# 5volt_rail.net
KiCad netlist of a schematic drawn in EAGLE
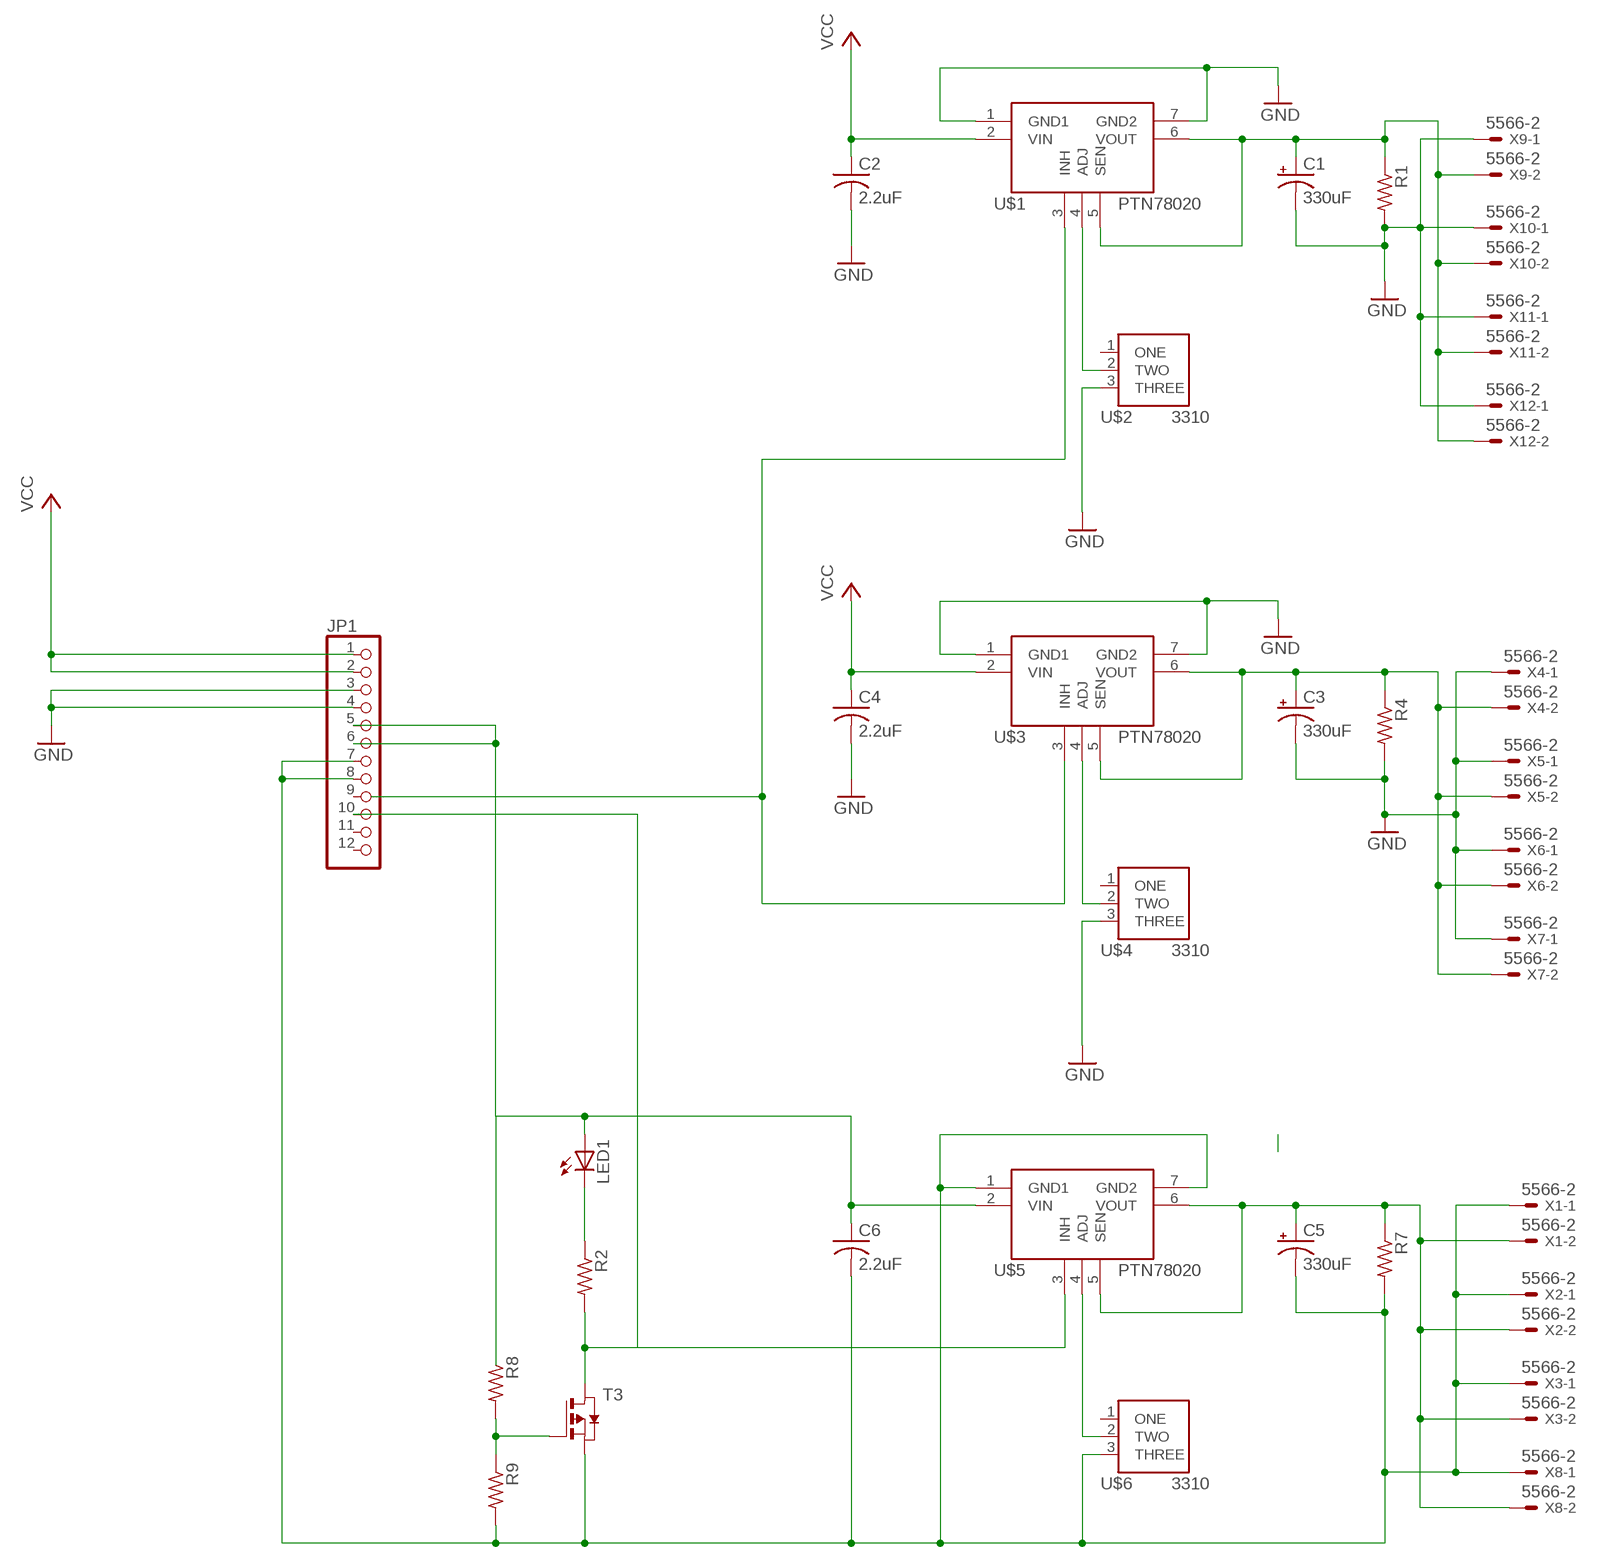
[diagram p0: schematic, sheet 1]

(export (version "E")
  (design (tool "Eeschema 10.0.6"))
  (components
    (comp (ref "C1")
      (value "330uF")
      (footprint "eagle-import:E5-10,5")
      (libsource (lib "eagle-import") (part "CPOL-USE5-10.5"))
    )
    (comp (ref "C2")
      (value "2.2uF")
      (footprint "eagle-import:C0805")
      (libsource (lib "eagle-import") (part "C-USC0805"))
    )
    (comp (ref "C3")
      (value "330uF")
      (footprint "eagle-import:E5-10,5")
      (libsource (lib "eagle-import") (part "CPOL-USE5-10.5"))
    )
    (comp (ref "C4")
      (value "2.2uF")
      (footprint "eagle-import:C0805")
      (libsource (lib "eagle-import") (part "C-USC0805"))
    )
    (comp (ref "C5")
      (value "330uF")
      (footprint "eagle-import:E5-10,5")
      (libsource (lib "eagle-import") (part "CPOL-USE5-10.5"))
    )
    (comp (ref "C6")
      (value "2.2uF")
      (footprint "eagle-import:C0805")
      (libsource (lib "eagle-import") (part "C-USC0805"))
    )
    (comp (ref "JP1")
      (value "PINHD-1X12")
      (footprint "eagle-import:1X12")
      (libsource (lib "eagle-import") (part "PINHD-1X12"))
    )
    (comp (ref "LED1")
      (value "LED5MM")
      (footprint "eagle-import:LED5MM")
      (libsource (lib "eagle-import") (part "LED5MM"))
    )
    (comp (ref "R1")
      (value "R-US_M0805")
      (footprint "eagle-import:M0805")
      (libsource (lib "eagle-import") (part "R-US_M0805"))
    )
    (comp (ref "R2")
      (value "R-US_M0805")
      (footprint "eagle-import:M0805")
      (libsource (lib "eagle-import") (part "R-US_M0805"))
    )
    (comp (ref "R4")
      (value "R-US_M0805")
      (footprint "eagle-import:M0805")
      (libsource (lib "eagle-import") (part "R-US_M0805"))
    )
    (comp (ref "R7")
      (value "R-US_M0805")
      (footprint "eagle-import:M0805")
      (libsource (lib "eagle-import") (part "R-US_M0805"))
    )
    (comp (ref "R8")
      (value "R-US_M0805")
      (footprint "eagle-import:M0805")
      (libsource (lib "eagle-import") (part "R-US_M0805"))
    )
    (comp (ref "R9")
      (value "R-US_M0805")
      (footprint "eagle-import:M0805")
      (libsource (lib "eagle-import") (part "R-US_M0805"))
    )
    (comp (ref "T3")
      (value "PMOSSOT223")
      (footprint "eagle-import:SOT223")
      (libsource (lib "eagle-import") (part "PMOSSOT223"))
    )
    (comp (ref "U$1")
      (value "PTH78020-SMD")
      (footprint "eagle-import:PTN78020-SND")
      (libsource (lib "eagle-import") (part "PTH78020-SMD"))
    )
    (comp (ref "U$2")
      (value "3310-001")
      (footprint "eagle-import:3310-001-TH")
      (libsource (lib "eagle-import") (part "3310-001"))
    )
    (comp (ref "U$3")
      (value "PTH78020-SMD")
      (footprint "eagle-import:PTN78020-SND")
      (libsource (lib "eagle-import") (part "PTH78020-SMD"))
    )
    (comp (ref "U$4")
      (value "3310-001")
      (footprint "eagle-import:3310-001-TH")
      (libsource (lib "eagle-import") (part "3310-001"))
    )
    (comp (ref "U$5")
      (value "PTH78020-SMD")
      (footprint "eagle-import:PTN78020-SND")
      (libsource (lib "eagle-import") (part "PTH78020-SMD"))
    )
    (comp (ref "U$6")
      (value "3310-001")
      (footprint "eagle-import:3310-001-TH")
      (libsource (lib "eagle-import") (part "3310-001"))
    )
    (comp (ref "X1")
      (value "5566-2")
      (footprint "eagle-import:5566-2")
      (libsource (lib "eagle-import") (part "5566-2"))
    )
    (comp (ref "X2")
      (value "5566-2")
      (footprint "eagle-import:5566-2")
      (libsource (lib "eagle-import") (part "5566-2"))
    )
    (comp (ref "X3")
      (value "5566-2")
      (footprint "eagle-import:5566-2")
      (libsource (lib "eagle-import") (part "5566-2"))
    )
    (comp (ref "X4")
      (value "5566-2")
      (footprint "eagle-import:5566-2")
      (libsource (lib "eagle-import") (part "5566-2"))
    )
    (comp (ref "X5")
      (value "5566-2")
      (footprint "eagle-import:5566-2")
      (libsource (lib "eagle-import") (part "5566-2"))
    )
    (comp (ref "X6")
      (value "5566-2")
      (footprint "eagle-import:5566-2")
      (libsource (lib "eagle-import") (part "5566-2"))
    )
    (comp (ref "X7")
      (value "5566-2")
      (footprint "eagle-import:5566-2")
      (libsource (lib "eagle-import") (part "5566-2"))
    )
    (comp (ref "X8")
      (value "5566-2")
      (footprint "eagle-import:5566-2")
      (libsource (lib "eagle-import") (part "5566-2"))
    )
    (comp (ref "X9")
      (value "5566-2")
      (footprint "eagle-import:5566-2")
      (libsource (lib "eagle-import") (part "5566-2"))
    )
    (comp (ref "X10")
      (value "5566-2")
      (footprint "eagle-import:5566-2")
      (libsource (lib "eagle-import") (part "5566-2"))
    )
    (comp (ref "X11")
      (value "5566-2")
      (footprint "eagle-import:5566-2")
      (libsource (lib "eagle-import") (part "5566-2"))
    )
    (comp (ref "X12")
      (value "5566-2")
      (footprint "eagle-import:5566-2")
      (libsource (lib "eagle-import") (part "5566-2"))
    )
  )
  (nets
    (net (code "1") (name "GND") (class "Default")
      (node (ref "C1") (pin "-") (pinfunction "-_-") (pintype "passive"))
      (node (ref "C2") (pin "2") (pinfunction "2_2") (pintype "passive"))
      (node (ref "C3") (pin "-") (pinfunction "-_-") (pintype "passive"))
      (node (ref "C4") (pin "2") (pinfunction "2_2") (pintype "passive"))
      (node (ref "JP1") (pin "3") (pinfunction "3_3") (pintype "passive"))
      (node (ref "JP1") (pin "4") (pinfunction "4_4") (pintype "passive"))
      (node (ref "R1") (pin "2") (pinfunction "2_2") (pintype "passive"))
      (node (ref "R4") (pin "2") (pinfunction "2_2") (pintype "passive"))
      (node (ref "U$1") (pin "1") (pinfunction "GND1_1") (pintype "bidirectional"))
      (node (ref "U$1") (pin "7") (pinfunction "GND2_7") (pintype "bidirectional"))
      (node (ref "U$2") (pin "3") (pinfunction "THREE_3") (pintype "bidirectional"))
      (node (ref "U$3") (pin "1") (pinfunction "GND1_1") (pintype "bidirectional"))
      (node (ref "U$3") (pin "7") (pinfunction "GND2_7") (pintype "bidirectional"))
      (node (ref "U$4") (pin "3") (pinfunction "THREE_3") (pintype "bidirectional"))
      (node (ref "X10") (pin "1") (pinfunction "S_1") (pintype "passive"))
      (node (ref "X11") (pin "1") (pinfunction "S_1") (pintype "passive"))
      (node (ref "X12") (pin "1") (pinfunction "S_1") (pintype "passive"))
      (node (ref "X4") (pin "1") (pinfunction "S_1") (pintype "passive"))
      (node (ref "X5") (pin "1") (pinfunction "S_1") (pintype "passive"))
      (node (ref "X6") (pin "1") (pinfunction "S_1") (pintype "passive"))
      (node (ref "X7") (pin "1") (pinfunction "S_1") (pintype "passive"))
      (node (ref "X9") (pin "1") (pinfunction "S_1") (pintype "passive"))
    )
    (net (code "2") (name "Net-(LED1-C)") (class "Default")
      (node (ref "LED1") (pin "K") (pinfunction "C_K") (pintype "passive"))
      (node (ref "R2") (pin "1") (pinfunction "1_1") (pintype "passive"))
    )
    (net (code "3") (name "Net-(T3-G)") (class "Default")
      (node (ref "R8") (pin "2") (pinfunction "2_2") (pintype "passive"))
      (node (ref "R9") (pin "1") (pinfunction "1_1") (pintype "passive"))
      (node (ref "T3") (pin "1") (pinfunction "G_1") (pintype "passive"))
    )
    (net (code "4") (name "Net-(T3-S)") (class "Default")
      (node (ref "C5") (pin "-") (pinfunction "-_-") (pintype "passive"))
      (node (ref "C6") (pin "2") (pinfunction "2_2") (pintype "passive"))
      (node (ref "JP1") (pin "7") (pinfunction "7_7") (pintype "passive"))
      (node (ref "JP1") (pin "8") (pinfunction "8_8") (pintype "passive"))
      (node (ref "R7") (pin "2") (pinfunction "2_2") (pintype "passive"))
      (node (ref "R9") (pin "2") (pinfunction "2_2") (pintype "passive"))
      (node (ref "T3") (pin "3") (pinfunction "S_3") (pintype "passive"))
      (node (ref "U$5") (pin "1") (pinfunction "GND1_1") (pintype "bidirectional"))
      (node (ref "U$5") (pin "7") (pinfunction "GND2_7") (pintype "bidirectional"))
      (node (ref "U$6") (pin "3") (pinfunction "THREE_3") (pintype "bidirectional"))
      (node (ref "X1") (pin "1") (pinfunction "S_1") (pintype "passive"))
      (node (ref "X2") (pin "1") (pinfunction "S_1") (pintype "passive"))
      (node (ref "X3") (pin "1") (pinfunction "S_1") (pintype "passive"))
      (node (ref "X8") (pin "1") (pinfunction "S_1") (pintype "passive"))
    )
    (net (code "5") (name "Net-(U$1-ADJ)") (class "Default")
      (node (ref "U$1") (pin "4") (pinfunction "ADJ_4") (pintype "bidirectional"))
      (node (ref "U$2") (pin "2") (pinfunction "TWO_2") (pintype "bidirectional"))
    )
    (net (code "6") (name "Net-(U$1-INH)") (class "Default")
      (node (ref "U$1") (pin "3") (pinfunction "INH_3") (pintype "bidirectional"))
      (node (ref "U$3") (pin "3") (pinfunction "INH_3") (pintype "bidirectional"))
    )
    (net (code "7") (name "Net-(U$1-SEN)") (class "Default")
      (node (ref "C1") (pin "+") (pinfunction "+_+") (pintype "passive"))
      (node (ref "R1") (pin "1") (pinfunction "1_1") (pintype "passive"))
      (node (ref "U$1") (pin "5") (pinfunction "SEN_5") (pintype "bidirectional"))
      (node (ref "U$1") (pin "6") (pinfunction "VOUT_6") (pintype "bidirectional"))
      (node (ref "X10") (pin "2") (pinfunction "S_2") (pintype "passive"))
      (node (ref "X11") (pin "2") (pinfunction "S_2") (pintype "passive"))
      (node (ref "X12") (pin "2") (pinfunction "S_2") (pintype "passive"))
      (node (ref "X9") (pin "2") (pinfunction "S_2") (pintype "passive"))
    )
    (net (code "8") (name "Net-(U$3-ADJ)") (class "Default")
      (node (ref "U$3") (pin "4") (pinfunction "ADJ_4") (pintype "bidirectional"))
      (node (ref "U$4") (pin "2") (pinfunction "TWO_2") (pintype "bidirectional"))
    )
    (net (code "9") (name "Net-(U$3-SEN)") (class "Default")
      (node (ref "C3") (pin "+") (pinfunction "+_+") (pintype "passive"))
      (node (ref "R4") (pin "1") (pinfunction "1_1") (pintype "passive"))
      (node (ref "U$3") (pin "5") (pinfunction "SEN_5") (pintype "bidirectional"))
      (node (ref "U$3") (pin "6") (pinfunction "VOUT_6") (pintype "bidirectional"))
      (node (ref "X4") (pin "2") (pinfunction "S_2") (pintype "passive"))
      (node (ref "X5") (pin "2") (pinfunction "S_2") (pintype "passive"))
      (node (ref "X6") (pin "2") (pinfunction "S_2") (pintype "passive"))
      (node (ref "X7") (pin "2") (pinfunction "S_2") (pintype "passive"))
    )
    (net (code "10") (name "Net-(U$5-ADJ)") (class "Default")
      (node (ref "U$5") (pin "4") (pinfunction "ADJ_4") (pintype "bidirectional"))
      (node (ref "U$6") (pin "2") (pinfunction "TWO_2") (pintype "bidirectional"))
    )
    (net (code "11") (name "Net-(U$5-INH)") (class "Default")
      (node (ref "JP1") (pin "10") (pinfunction "10_10") (pintype "passive"))
      (node (ref "R2") (pin "2") (pinfunction "2_2") (pintype "passive"))
      (node (ref "T3") (pin "2") (pinfunction "D_2") (pintype "passive"))
      (node (ref "T3") (pin "4") (pinfunction "D_4") (pintype "passive"))
      (node (ref "U$5") (pin "3") (pinfunction "INH_3") (pintype "bidirectional"))
    )
    (net (code "12") (name "Net-(U$5-SEN)") (class "Default")
      (node (ref "C5") (pin "+") (pinfunction "+_+") (pintype "passive"))
      (node (ref "R7") (pin "1") (pinfunction "1_1") (pintype "passive"))
      (node (ref "U$5") (pin "5") (pinfunction "SEN_5") (pintype "bidirectional"))
      (node (ref "U$5") (pin "6") (pinfunction "VOUT_6") (pintype "bidirectional"))
      (node (ref "X1") (pin "2") (pinfunction "S_2") (pintype "passive"))
      (node (ref "X2") (pin "2") (pinfunction "S_2") (pintype "passive"))
      (node (ref "X3") (pin "2") (pinfunction "S_2") (pintype "passive"))
      (node (ref "X8") (pin "2") (pinfunction "S_2") (pintype "passive"))
    )
    (net (code "13") (name "Net-(U$5-VIN)") (class "Default")
      (node (ref "C6") (pin "1") (pinfunction "1_1") (pintype "passive"))
      (node (ref "JP1") (pin "5") (pinfunction "5_5") (pintype "passive"))
      (node (ref "JP1") (pin "6") (pinfunction "6_6") (pintype "passive"))
      (node (ref "LED1") (pin "A") (pinfunction "A_A") (pintype "passive"))
      (node (ref "U$5") (pin "2") (pinfunction "VIN_2") (pintype "bidirectional"))
    )
    (net (code "14") (name "VCC") (class "Default")
      (node (ref "C2") (pin "1") (pinfunction "1_1") (pintype "passive"))
      (node (ref "C4") (pin "1") (pinfunction "1_1") (pintype "passive"))
      (node (ref "JP1") (pin "1") (pinfunction "1_1") (pintype "passive"))
      (node (ref "JP1") (pin "2") (pinfunction "2_2") (pintype "passive"))
      (node (ref "U$1") (pin "2") (pinfunction "VIN_2") (pintype "bidirectional"))
      (node (ref "U$3") (pin "2") (pinfunction "VIN_2") (pintype "bidirectional"))
    )
    (net (code "15") (name "unconnected-(JP1-Pad9)") (class "Default")
      (node (ref "JP1") (pin "9") (pinfunction "9_9") (pintype "passive"))
    )
    (net (code "16") (name "unconnected-(JP1-Pad11)") (class "Default")
      (node (ref "JP1") (pin "11") (pinfunction "11_11") (pintype "passive"))
    )
    (net (code "17") (name "unconnected-(JP1-Pad12)") (class "Default")
      (node (ref "JP1") (pin "12") (pinfunction "12_12") (pintype "passive"))
    )
    (net (code "18") (name "unconnected-(R8-Pad1)") (class "Default")
      (node (ref "R8") (pin "1") (pinfunction "1_1") (pintype "passive"))
    )
    (net (code "19") (name "unconnected-(U$2-ONE-Pad1)") (class "Default")
      (node (ref "U$2") (pin "1") (pinfunction "ONE_1") (pintype "bidirectional"))
    )
    (net (code "20") (name "unconnected-(U$4-ONE-Pad1)") (class "Default")
      (node (ref "U$4") (pin "1") (pinfunction "ONE_1") (pintype "bidirectional"))
    )
    (net (code "21") (name "unconnected-(U$6-ONE-Pad1)") (class "Default")
      (node (ref "U$6") (pin "1") (pinfunction "ONE_1") (pintype "bidirectional"))
    )
  )
)
